# W107X.net
KiCad netlist of a schematic drawn in EAGLE
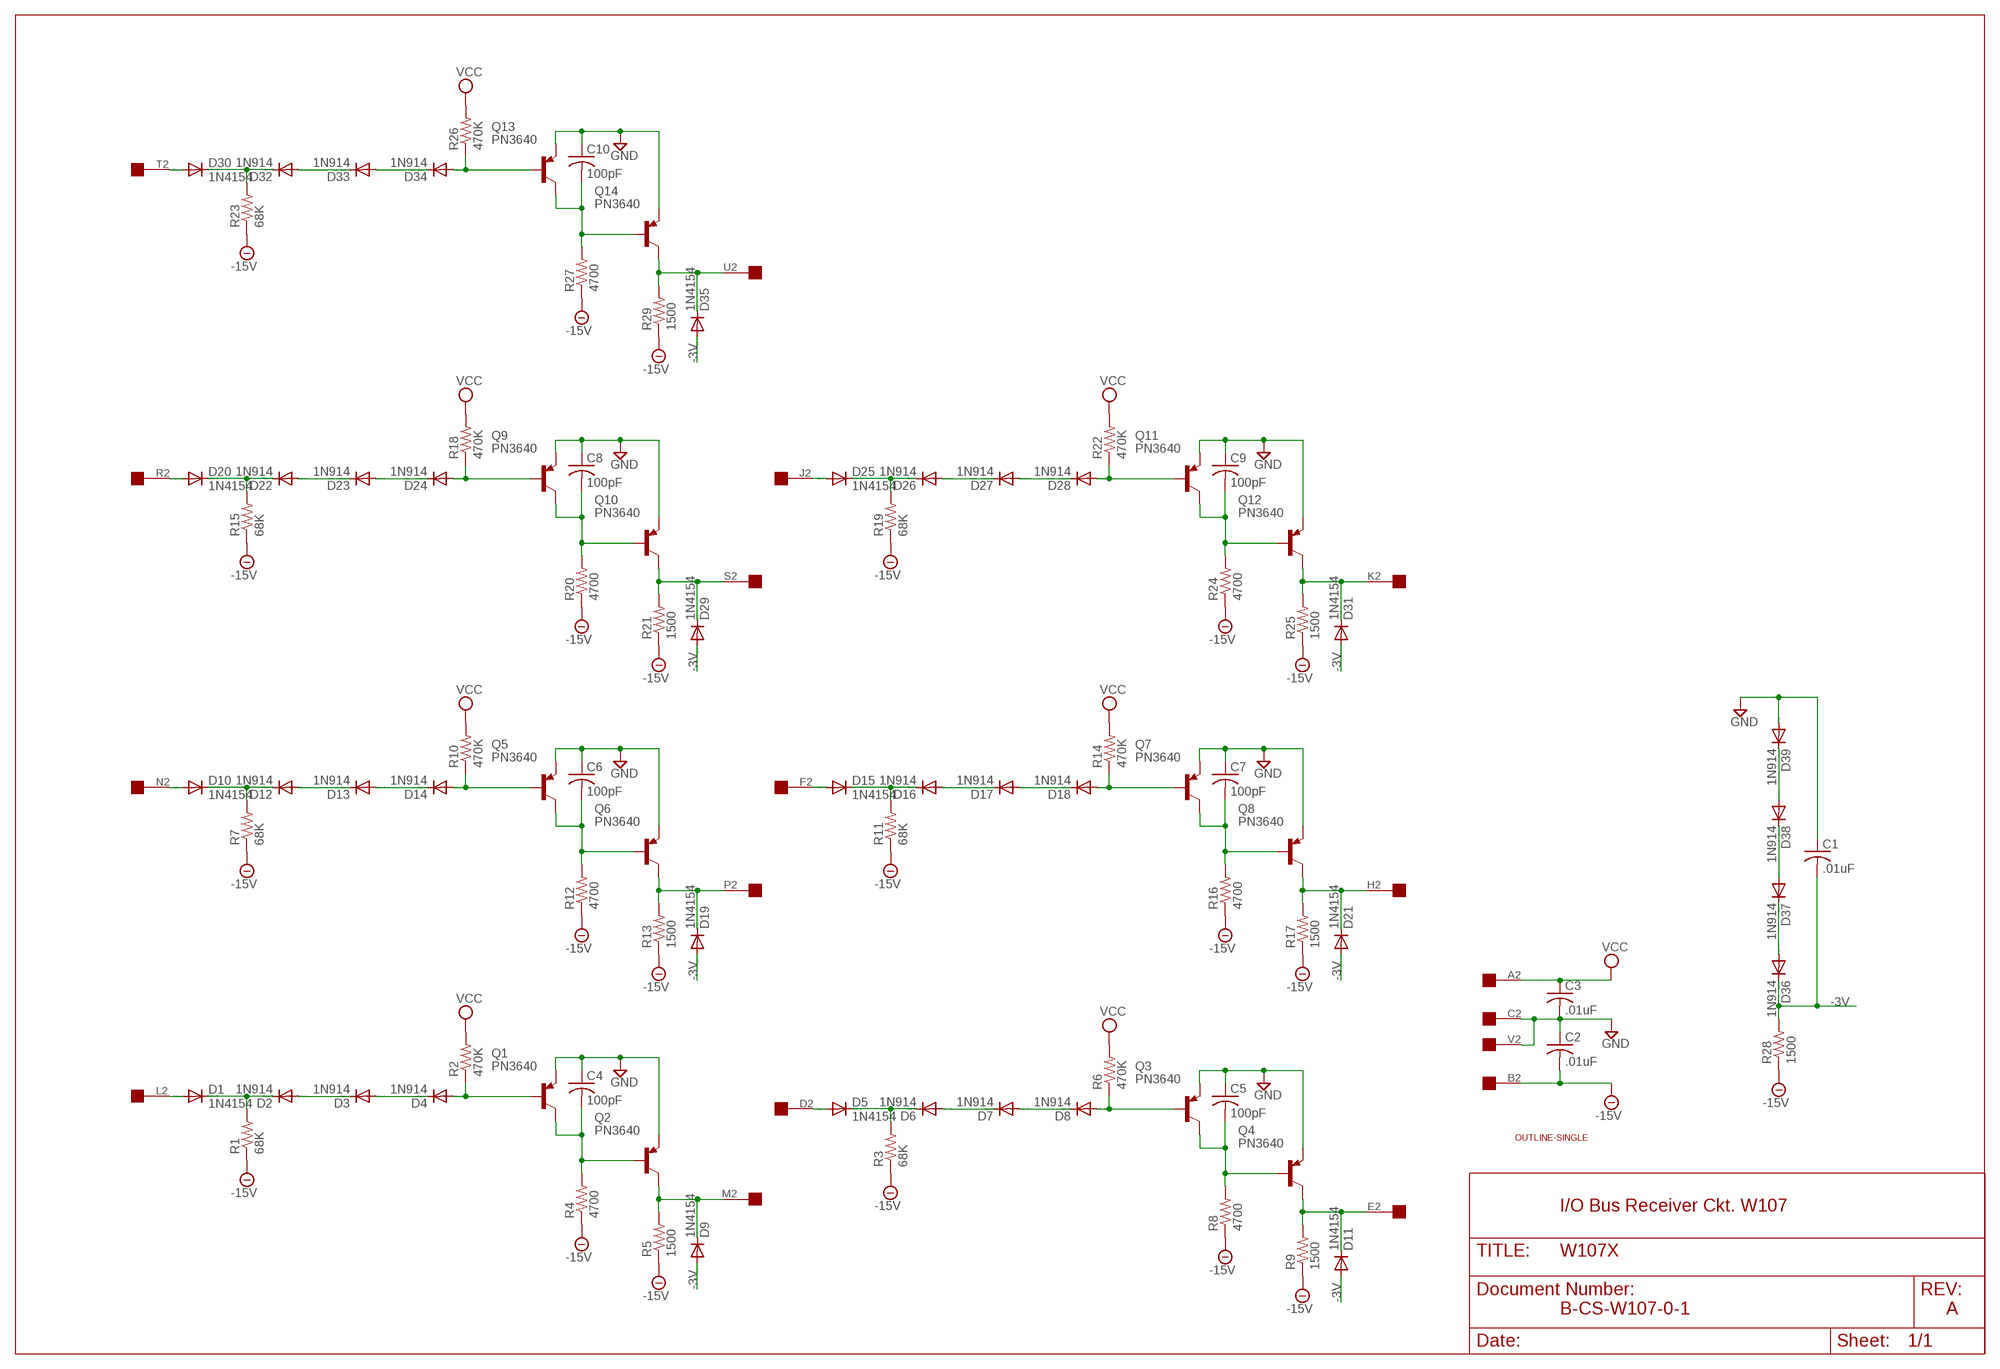
[diagram p0: schematic, sheet 1]

(export (version "E")
  (design (tool "Eeschema 10.0.6"))
  (components
    (comp (ref "C1")
      (value ".01uF")
      (footprint "eagle-import:C063-025X075")
      (libsource (lib "eagle-import") (part "C-US"))
    )
    (comp (ref "C2")
      (value ".01uF")
      (footprint "eagle-import:C063-025X075")
      (libsource (lib "eagle-import") (part "C-US"))
    )
    (comp (ref "C3")
      (value ".01uF")
      (footprint "eagle-import:C063-025X075")
      (libsource (lib "eagle-import") (part "C-US"))
    )
    (comp (ref "C4")
      (value "100pF")
      (footprint "eagle-import:C063-025X075")
      (libsource (lib "eagle-import") (part "C-US"))
    )
    (comp (ref "C5")
      (value "100pF")
      (footprint "eagle-import:C063-025X075")
      (libsource (lib "eagle-import") (part "C-US"))
    )
    (comp (ref "C6")
      (value "100pF")
      (footprint "eagle-import:C063-025X075")
      (libsource (lib "eagle-import") (part "C-US"))
    )
    (comp (ref "C7")
      (value "100pF")
      (footprint "eagle-import:C063-025X075")
      (libsource (lib "eagle-import") (part "C-US"))
    )
    (comp (ref "C8")
      (value "100pF")
      (footprint "eagle-import:C063-025X075")
      (libsource (lib "eagle-import") (part "C-US"))
    )
    (comp (ref "C9")
      (value "100pF")
      (footprint "eagle-import:C063-025X075")
      (libsource (lib "eagle-import") (part "C-US"))
    )
    (comp (ref "C10")
      (value "100pF")
      (footprint "eagle-import:C063-025X075")
      (libsource (lib "eagle-import") (part "C-US"))
    )
    (comp (ref "D1")
      (value "1N4154")
      (footprint "eagle-import:DO35-10")
      (libsource (lib "eagle-import") (part "DIODE-DO35-10"))
    )
    (comp (ref "D2")
      (value "1N914")
      (footprint "eagle-import:DO35-10")
      (libsource (lib "eagle-import") (part "DIODE-DO35-10"))
    )
    (comp (ref "D3")
      (value "1N914")
      (footprint "eagle-import:DO35-10")
      (libsource (lib "eagle-import") (part "DIODE-DO35-10"))
    )
    (comp (ref "D4")
      (value "1N914")
      (footprint "eagle-import:DO35-10")
      (libsource (lib "eagle-import") (part "DIODE-DO35-10"))
    )
    (comp (ref "D5")
      (value "1N4154")
      (footprint "eagle-import:DO35-10")
      (libsource (lib "eagle-import") (part "DIODE-DO35-10"))
    )
    (comp (ref "D6")
      (value "1N914")
      (footprint "eagle-import:DO35-10")
      (libsource (lib "eagle-import") (part "DIODE-DO35-10"))
    )
    (comp (ref "D7")
      (value "1N914")
      (footprint "eagle-import:DO35-10")
      (libsource (lib "eagle-import") (part "DIODE-DO35-10"))
    )
    (comp (ref "D8")
      (value "1N914")
      (footprint "eagle-import:DO35-10")
      (libsource (lib "eagle-import") (part "DIODE-DO35-10"))
    )
    (comp (ref "D9")
      (value "1N4154")
      (footprint "eagle-import:DO35-10")
      (libsource (lib "eagle-import") (part "DIODE-DO35-10"))
    )
    (comp (ref "D10")
      (value "1N4154")
      (footprint "eagle-import:DO35-10")
      (libsource (lib "eagle-import") (part "DIODE-DO35-10"))
    )
    (comp (ref "D11")
      (value "1N4154")
      (footprint "eagle-import:DO35-10")
      (libsource (lib "eagle-import") (part "DIODE-DO35-10"))
    )
    (comp (ref "D12")
      (value "1N914")
      (footprint "eagle-import:DO35-10")
      (libsource (lib "eagle-import") (part "DIODE-DO35-10"))
    )
    (comp (ref "D13")
      (value "1N914")
      (footprint "eagle-import:DO35-10")
      (libsource (lib "eagle-import") (part "DIODE-DO35-10"))
    )
    (comp (ref "D14")
      (value "1N914")
      (footprint "eagle-import:DO35-10")
      (libsource (lib "eagle-import") (part "DIODE-DO35-10"))
    )
    (comp (ref "D15")
      (value "1N4154")
      (footprint "eagle-import:DO35-10")
      (libsource (lib "eagle-import") (part "DIODE-DO35-10"))
    )
    (comp (ref "D16")
      (value "1N914")
      (footprint "eagle-import:DO35-10")
      (libsource (lib "eagle-import") (part "DIODE-DO35-10"))
    )
    (comp (ref "D17")
      (value "1N914")
      (footprint "eagle-import:DO35-10")
      (libsource (lib "eagle-import") (part "DIODE-DO35-10"))
    )
    (comp (ref "D18")
      (value "1N914")
      (footprint "eagle-import:DO35-10")
      (libsource (lib "eagle-import") (part "DIODE-DO35-10"))
    )
    (comp (ref "D19")
      (value "1N4154")
      (footprint "eagle-import:DO35-10")
      (libsource (lib "eagle-import") (part "DIODE-DO35-10"))
    )
    (comp (ref "D20")
      (value "1N4154")
      (footprint "eagle-import:DO35-10")
      (libsource (lib "eagle-import") (part "DIODE-DO35-10"))
    )
    (comp (ref "D21")
      (value "1N4154")
      (footprint "eagle-import:DO35-10")
      (libsource (lib "eagle-import") (part "DIODE-DO35-10"))
    )
    (comp (ref "D22")
      (value "1N914")
      (footprint "eagle-import:DO35-10")
      (libsource (lib "eagle-import") (part "DIODE-DO35-10"))
    )
    (comp (ref "D23")
      (value "1N914")
      (footprint "eagle-import:DO35-10")
      (libsource (lib "eagle-import") (part "DIODE-DO35-10"))
    )
    (comp (ref "D24")
      (value "1N914")
      (footprint "eagle-import:DO35-10")
      (libsource (lib "eagle-import") (part "DIODE-DO35-10"))
    )
    (comp (ref "D25")
      (value "1N4154")
      (footprint "eagle-import:DO35-10")
      (libsource (lib "eagle-import") (part "DIODE-DO35-10"))
    )
    (comp (ref "D26")
      (value "1N914")
      (footprint "eagle-import:DO35-10")
      (libsource (lib "eagle-import") (part "DIODE-DO35-10"))
    )
    (comp (ref "D27")
      (value "1N914")
      (footprint "eagle-import:DO35-10")
      (libsource (lib "eagle-import") (part "DIODE-DO35-10"))
    )
    (comp (ref "D28")
      (value "1N914")
      (footprint "eagle-import:DO35-10")
      (libsource (lib "eagle-import") (part "DIODE-DO35-10"))
    )
    (comp (ref "D29")
      (value "1N4154")
      (footprint "eagle-import:DO35-10")
      (libsource (lib "eagle-import") (part "DIODE-DO35-10"))
    )
    (comp (ref "D30")
      (value "1N4154")
      (footprint "eagle-import:DO35-10")
      (libsource (lib "eagle-import") (part "DIODE-DO35-10"))
    )
    (comp (ref "D31")
      (value "1N4154")
      (footprint "eagle-import:DO35-10")
      (libsource (lib "eagle-import") (part "DIODE-DO35-10"))
    )
    (comp (ref "D32")
      (value "1N914")
      (footprint "eagle-import:DO35-10")
      (libsource (lib "eagle-import") (part "DIODE-DO35-10"))
    )
    (comp (ref "D33")
      (value "1N914")
      (footprint "eagle-import:DO35-10")
      (libsource (lib "eagle-import") (part "DIODE-DO35-10"))
    )
    (comp (ref "D34")
      (value "1N914")
      (footprint "eagle-import:DO35-10")
      (libsource (lib "eagle-import") (part "DIODE-DO35-10"))
    )
    (comp (ref "D35")
      (value "1N4154")
      (footprint "eagle-import:DO35-10")
      (libsource (lib "eagle-import") (part "DIODE-DO35-10"))
    )
    (comp (ref "D36")
      (value "1N914")
      (footprint "eagle-import:DO35-10")
      (libsource (lib "eagle-import") (part "DIODE-DO35-10"))
    )
    (comp (ref "D37")
      (value "1N914")
      (footprint "eagle-import:DO35-10")
      (libsource (lib "eagle-import") (part "DIODE-DO35-10"))
    )
    (comp (ref "D38")
      (value "1N914")
      (footprint "eagle-import:DO35-10")
      (libsource (lib "eagle-import") (part "DIODE-DO35-10"))
    )
    (comp (ref "D39")
      (value "1N914")
      (footprint "eagle-import:DO35-10")
      (libsource (lib "eagle-import") (part "DIODE-DO35-10"))
    )
    (comp (ref "Q1")
      (value "PN3640")
      (footprint "eagle-import:TO5")
      (libsource (lib "eagle-import") (part "-PNP-TO5"))
    )
    (comp (ref "Q2")
      (value "PN3640")
      (footprint "eagle-import:TO5")
      (libsource (lib "eagle-import") (part "-PNP-TO5"))
    )
    (comp (ref "Q3")
      (value "PN3640")
      (footprint "eagle-import:TO5")
      (libsource (lib "eagle-import") (part "-PNP-TO5"))
    )
    (comp (ref "Q4")
      (value "PN3640")
      (footprint "eagle-import:TO5")
      (libsource (lib "eagle-import") (part "-PNP-TO5"))
    )
    (comp (ref "Q5")
      (value "PN3640")
      (footprint "eagle-import:TO5")
      (libsource (lib "eagle-import") (part "-PNP-TO5"))
    )
    (comp (ref "Q6")
      (value "PN3640")
      (footprint "eagle-import:TO5")
      (libsource (lib "eagle-import") (part "-PNP-TO5"))
    )
    (comp (ref "Q7")
      (value "PN3640")
      (footprint "eagle-import:TO5")
      (libsource (lib "eagle-import") (part "-PNP-TO5"))
    )
    (comp (ref "Q8")
      (value "PN3640")
      (footprint "eagle-import:TO5")
      (libsource (lib "eagle-import") (part "-PNP-TO5"))
    )
    (comp (ref "Q9")
      (value "PN3640")
      (footprint "eagle-import:TO5")
      (libsource (lib "eagle-import") (part "-PNP-TO5"))
    )
    (comp (ref "Q10")
      (value "PN3640")
      (footprint "eagle-import:TO5")
      (libsource (lib "eagle-import") (part "-PNP-TO5"))
    )
    (comp (ref "Q11")
      (value "PN3640")
      (footprint "eagle-import:TO5")
      (libsource (lib "eagle-import") (part "-PNP-TO5"))
    )
    (comp (ref "Q12")
      (value "PN3640")
      (footprint "eagle-import:TO5")
      (libsource (lib "eagle-import") (part "-PNP-TO5"))
    )
    (comp (ref "Q13")
      (value "PN3640")
      (footprint "eagle-import:TO5")
      (libsource (lib "eagle-import") (part "-PNP-TO5"))
    )
    (comp (ref "Q14")
      (value "PN3640")
      (footprint "eagle-import:TO5")
      (libsource (lib "eagle-import") (part "-PNP-TO5"))
    )
    (comp (ref "R1")
      (value "68K")
      (footprint "eagle-import:0207_10")
      (libsource (lib "eagle-import") (part "R-US_0207/10"))
    )
    (comp (ref "R2")
      (value "470K")
      (footprint "eagle-import:0207_10")
      (libsource (lib "eagle-import") (part "R-US_0207/10"))
    )
    (comp (ref "R3")
      (value "68K")
      (footprint "eagle-import:0207_10")
      (libsource (lib "eagle-import") (part "R-US_0207/10"))
    )
    (comp (ref "R4")
      (value "4700")
      (footprint "eagle-import:0207_10")
      (libsource (lib "eagle-import") (part "R-US_0207/10"))
    )
    (comp (ref "R5")
      (value "1500")
      (footprint "eagle-import:0207_10")
      (libsource (lib "eagle-import") (part "R-US_0207/10"))
    )
    (comp (ref "R6")
      (value "470K")
      (footprint "eagle-import:0207_10")
      (libsource (lib "eagle-import") (part "R-US_0207/10"))
    )
    (comp (ref "R7")
      (value "68K")
      (footprint "eagle-import:0207_10")
      (libsource (lib "eagle-import") (part "R-US_0207/10"))
    )
    (comp (ref "R8")
      (value "4700")
      (footprint "eagle-import:0207_10")
      (libsource (lib "eagle-import") (part "R-US_0207/10"))
    )
    (comp (ref "R9")
      (value "1500")
      (footprint "eagle-import:0207_10")
      (libsource (lib "eagle-import") (part "R-US_0207/10"))
    )
    (comp (ref "R10")
      (value "470K")
      (footprint "eagle-import:0207_10")
      (libsource (lib "eagle-import") (part "R-US_0207/10"))
    )
    (comp (ref "R11")
      (value "68K")
      (footprint "eagle-import:0207_10")
      (libsource (lib "eagle-import") (part "R-US_0207/10"))
    )
    (comp (ref "R12")
      (value "4700")
      (footprint "eagle-import:0207_10")
      (libsource (lib "eagle-import") (part "R-US_0207/10"))
    )
    (comp (ref "R13")
      (value "1500")
      (footprint "eagle-import:0207_10")
      (libsource (lib "eagle-import") (part "R-US_0207/10"))
    )
    (comp (ref "R14")
      (value "470K")
      (footprint "eagle-import:0207_10")
      (libsource (lib "eagle-import") (part "R-US_0207/10"))
    )
    (comp (ref "R15")
      (value "68K")
      (footprint "eagle-import:0207_10")
      (libsource (lib "eagle-import") (part "R-US_0207/10"))
    )
    (comp (ref "R16")
      (value "4700")
      (footprint "eagle-import:0207_10")
      (libsource (lib "eagle-import") (part "R-US_0207/10"))
    )
    (comp (ref "R17")
      (value "1500")
      (footprint "eagle-import:0207_10")
      (libsource (lib "eagle-import") (part "R-US_0207/10"))
    )
    (comp (ref "R18")
      (value "470K")
      (footprint "eagle-import:0207_10")
      (libsource (lib "eagle-import") (part "R-US_0207/10"))
    )
    (comp (ref "R19")
      (value "68K")
      (footprint "eagle-import:0207_10")
      (libsource (lib "eagle-import") (part "R-US_0207/10"))
    )
    (comp (ref "R20")
      (value "4700")
      (footprint "eagle-import:0207_10")
      (libsource (lib "eagle-import") (part "R-US_0207/10"))
    )
    (comp (ref "R21")
      (value "1500")
      (footprint "eagle-import:0207_10")
      (libsource (lib "eagle-import") (part "R-US_0207/10"))
    )
    (comp (ref "R22")
      (value "470K")
      (footprint "eagle-import:0207_10")
      (libsource (lib "eagle-import") (part "R-US_0207/10"))
    )
    (comp (ref "R23")
      (value "68K")
      (footprint "eagle-import:0207_10")
      (libsource (lib "eagle-import") (part "R-US_0207/10"))
    )
    (comp (ref "R24")
      (value "4700")
      (footprint "eagle-import:0207_10")
      (libsource (lib "eagle-import") (part "R-US_0207/10"))
    )
    (comp (ref "R25")
      (value "1500")
      (footprint "eagle-import:0207_10")
      (libsource (lib "eagle-import") (part "R-US_0207/10"))
    )
    (comp (ref "R26")
      (value "470K")
      (footprint "eagle-import:0207_10")
      (libsource (lib "eagle-import") (part "R-US_0207/10"))
    )
    (comp (ref "R27")
      (value "4700")
      (footprint "eagle-import:0207_10")
      (libsource (lib "eagle-import") (part "R-US_0207/10"))
    )
    (comp (ref "R28")
      (value "1500")
      (footprint "eagle-import:0207_10")
      (libsource (lib "eagle-import") (part "R-US_0207/10"))
    )
    (comp (ref "R29")
      (value "1500")
      (footprint "eagle-import:0207_10")
      (libsource (lib "eagle-import") (part "R-US_0207/10"))
    )
    (comp (ref "U$1")
      (value "OUTLINE-SINGLE")
      (footprint "eagle-import:SINGLE")
      (libsource (lib "eagle-import") (part "OUTLINE-SINGLE"))
    )
    (comp (ref "U$2")
      (value "EDGE-1")
      (footprint "eagle-import:EDGE-CON1")
      (libsource (lib "eagle-import") (part "EDGE-1"))
    )
  )
  (nets
    (net (code "1") (name "-15V") (class "Default")
      (node (ref "C2") (pin "2") (pinfunction "2_2") (pintype "passive"))
      (node (ref "R1") (pin "1") (pinfunction "1_1") (pintype "passive"))
      (node (ref "R11") (pin "1") (pinfunction "1_1") (pintype "passive"))
      (node (ref "R12") (pin "1") (pinfunction "1_1") (pintype "passive"))
      (node (ref "R13") (pin "1") (pinfunction "1_1") (pintype "passive"))
      (node (ref "R15") (pin "1") (pinfunction "1_1") (pintype "passive"))
      (node (ref "R16") (pin "1") (pinfunction "1_1") (pintype "passive"))
      (node (ref "R17") (pin "1") (pinfunction "1_1") (pintype "passive"))
      (node (ref "R19") (pin "1") (pinfunction "1_1") (pintype "passive"))
      (node (ref "R20") (pin "1") (pinfunction "1_1") (pintype "passive"))
      (node (ref "R21") (pin "1") (pinfunction "1_1") (pintype "passive"))
      (node (ref "R23") (pin "1") (pinfunction "1_1") (pintype "passive"))
      (node (ref "R24") (pin "1") (pinfunction "1_1") (pintype "passive"))
      (node (ref "R25") (pin "1") (pinfunction "1_1") (pintype "passive"))
      (node (ref "R27") (pin "1") (pinfunction "1_1") (pintype "passive"))
      (node (ref "R28") (pin "1") (pinfunction "1_1") (pintype "passive"))
      (node (ref "R29") (pin "1") (pinfunction "1_1") (pintype "passive"))
      (node (ref "R3") (pin "1") (pinfunction "1_1") (pintype "passive"))
      (node (ref "R4") (pin "1") (pinfunction "1_1") (pintype "passive"))
      (node (ref "R5") (pin "1") (pinfunction "1_1") (pintype "passive"))
      (node (ref "R7") (pin "1") (pinfunction "1_1") (pintype "passive"))
      (node (ref "R8") (pin "1") (pinfunction "1_1") (pintype "passive"))
      (node (ref "R9") (pin "1") (pinfunction "1_1") (pintype "passive"))
      (node (ref "U$2") (pin "B2") (pinfunction "1_B2") (pintype "bidirectional"))
    )
    (net (code "2") (name "/-3V") (class "Default")
      (node (ref "C1") (pin "2") (pinfunction "2_2") (pintype "passive"))
      (node (ref "D11") (pin "A") (pinfunction "A_A") (pintype "passive"))
      (node (ref "D19") (pin "A") (pinfunction "A_A") (pintype "passive"))
      (node (ref "D21") (pin "A") (pinfunction "A_A") (pintype "passive"))
      (node (ref "D29") (pin "A") (pinfunction "A_A") (pintype "passive"))
      (node (ref "D31") (pin "A") (pinfunction "A_A") (pintype "passive"))
      (node (ref "D35") (pin "A") (pinfunction "A_A") (pintype "passive"))
      (node (ref "D36") (pin "C") (pinfunction "C_C") (pintype "passive"))
      (node (ref "D9") (pin "A") (pinfunction "A_A") (pintype "passive"))
      (node (ref "R28") (pin "2") (pinfunction "2_2") (pintype "passive"))
    )
    (net (code "3") (name "GND") (class "Default")
      (node (ref "C1") (pin "1") (pinfunction "1_1") (pintype "passive"))
      (node (ref "C10") (pin "1") (pinfunction "1_1") (pintype "passive"))
      (node (ref "C2") (pin "1") (pinfunction "1_1") (pintype "passive"))
      (node (ref "C3") (pin "2") (pinfunction "2_2") (pintype "passive"))
      (node (ref "C4") (pin "1") (pinfunction "1_1") (pintype "passive"))
      (node (ref "C5") (pin "1") (pinfunction "1_1") (pintype "passive"))
      (node (ref "C6") (pin "1") (pinfunction "1_1") (pintype "passive"))
      (node (ref "C7") (pin "1") (pinfunction "1_1") (pintype "passive"))
      (node (ref "C8") (pin "1") (pinfunction "1_1") (pintype "passive"))
      (node (ref "C9") (pin "1") (pinfunction "1_1") (pintype "passive"))
      (node (ref "D39") (pin "A") (pinfunction "A_A") (pintype "passive"))
      (node (ref "Q1") (pin "1") (pinfunction "E_1") (pintype "passive"))
      (node (ref "Q10") (pin "1") (pinfunction "E_1") (pintype "passive"))
      (node (ref "Q11") (pin "1") (pinfunction "E_1") (pintype "passive"))
      (node (ref "Q12") (pin "1") (pinfunction "E_1") (pintype "passive"))
      (node (ref "Q13") (pin "1") (pinfunction "E_1") (pintype "passive"))
      (node (ref "Q14") (pin "1") (pinfunction "E_1") (pintype "passive"))
      (node (ref "Q2") (pin "1") (pinfunction "E_1") (pintype "passive"))
      (node (ref "Q3") (pin "1") (pinfunction "E_1") (pintype "passive"))
      (node (ref "Q4") (pin "1") (pinfunction "E_1") (pintype "passive"))
      (node (ref "Q5") (pin "1") (pinfunction "E_1") (pintype "passive"))
      (node (ref "Q6") (pin "1") (pinfunction "E_1") (pintype "passive"))
      (node (ref "Q7") (pin "1") (pinfunction "E_1") (pintype "passive"))
      (node (ref "Q8") (pin "1") (pinfunction "E_1") (pintype "passive"))
      (node (ref "Q9") (pin "1") (pinfunction "E_1") (pintype "passive"))
      (node (ref "U$2") (pin "C2") (pinfunction "1_C2") (pintype "bidirectional"))
      (node (ref "U$2") (pin "V2") (pinfunction "1_V2") (pintype "bidirectional"))
    )
    (net (code "4") (name "Net-(D1-PadC)") (class "Default")
      (node (ref "D1") (pin "C") (pinfunction "C_C") (pintype "passive"))
      (node (ref "D2") (pin "C") (pinfunction "C_C") (pintype "passive"))
      (node (ref "R1") (pin "2") (pinfunction "2_2") (pintype "passive"))
    )
    (net (code "5") (name "Net-(D2-PadA)") (class "Default")
      (node (ref "D2") (pin "A") (pinfunction "A_A") (pintype "passive"))
      (node (ref "D3") (pin "C") (pinfunction "C_C") (pintype "passive"))
    )
    (net (code "6") (name "Net-(D3-PadA)") (class "Default")
      (node (ref "D3") (pin "A") (pinfunction "A_A") (pintype "passive"))
      (node (ref "D4") (pin "C") (pinfunction "C_C") (pintype "passive"))
    )
    (net (code "7") (name "Net-(D5-PadC)") (class "Default")
      (node (ref "D5") (pin "C") (pinfunction "C_C") (pintype "passive"))
      (node (ref "D6") (pin "C") (pinfunction "C_C") (pintype "passive"))
      (node (ref "R3") (pin "2") (pinfunction "2_2") (pintype "passive"))
    )
    (net (code "8") (name "Net-(D6-PadA)") (class "Default")
      (node (ref "D6") (pin "A") (pinfunction "A_A") (pintype "passive"))
      (node (ref "D7") (pin "C") (pinfunction "C_C") (pintype "passive"))
    )
    (net (code "9") (name "Net-(D7-PadA)") (class "Default")
      (node (ref "D7") (pin "A") (pinfunction "A_A") (pintype "passive"))
      (node (ref "D8") (pin "C") (pinfunction "C_C") (pintype "passive"))
    )
    (net (code "10") (name "Net-(D10-PadC)") (class "Default")
      (node (ref "D10") (pin "C") (pinfunction "C_C") (pintype "passive"))
      (node (ref "D12") (pin "C") (pinfunction "C_C") (pintype "passive"))
      (node (ref "R7") (pin "2") (pinfunction "2_2") (pintype "passive"))
    )
    (net (code "11") (name "Net-(D12-PadA)") (class "Default")
      (node (ref "D12") (pin "A") (pinfunction "A_A") (pintype "passive"))
      (node (ref "D13") (pin "C") (pinfunction "C_C") (pintype "passive"))
    )
    (net (code "12") (name "Net-(D13-PadA)") (class "Default")
      (node (ref "D13") (pin "A") (pinfunction "A_A") (pintype "passive"))
      (node (ref "D14") (pin "C") (pinfunction "C_C") (pintype "passive"))
    )
    (net (code "13") (name "Net-(D15-PadC)") (class "Default")
      (node (ref "D15") (pin "C") (pinfunction "C_C") (pintype "passive"))
      (node (ref "D16") (pin "C") (pinfunction "C_C") (pintype "passive"))
      (node (ref "R11") (pin "2") (pinfunction "2_2") (pintype "passive"))
    )
    (net (code "14") (name "Net-(D16-PadA)") (class "Default")
      (node (ref "D16") (pin "A") (pinfunction "A_A") (pintype "passive"))
      (node (ref "D17") (pin "C") (pinfunction "C_C") (pintype "passive"))
    )
    (net (code "15") (name "Net-(D17-PadA)") (class "Default")
      (node (ref "D17") (pin "A") (pinfunction "A_A") (pintype "passive"))
      (node (ref "D18") (pin "C") (pinfunction "C_C") (pintype "passive"))
    )
    (net (code "16") (name "Net-(D20-PadC)") (class "Default")
      (node (ref "D20") (pin "C") (pinfunction "C_C") (pintype "passive"))
      (node (ref "D22") (pin "C") (pinfunction "C_C") (pintype "passive"))
      (node (ref "R15") (pin "2") (pinfunction "2_2") (pintype "passive"))
    )
    (net (code "17") (name "Net-(D22-PadA)") (class "Default")
      (node (ref "D22") (pin "A") (pinfunction "A_A") (pintype "passive"))
      (node (ref "D23") (pin "C") (pinfunction "C_C") (pintype "passive"))
    )
    (net (code "18") (name "Net-(D23-PadA)") (class "Default")
      (node (ref "D23") (pin "A") (pinfunction "A_A") (pintype "passive"))
      (node (ref "D24") (pin "C") (pinfunction "C_C") (pintype "passive"))
    )
    (net (code "19") (name "Net-(D25-PadC)") (class "Default")
      (node (ref "D25") (pin "C") (pinfunction "C_C") (pintype "passive"))
      (node (ref "D26") (pin "C") (pinfunction "C_C") (pintype "passive"))
      (node (ref "R19") (pin "2") (pinfunction "2_2") (pintype "passive"))
    )
    (net (code "20") (name "Net-(D26-PadA)") (class "Default")
      (node (ref "D26") (pin "A") (pinfunction "A_A") (pintype "passive"))
      (node (ref "D27") (pin "C") (pinfunction "C_C") (pintype "passive"))
    )
    (net (code "21") (name "Net-(D27-PadA)") (class "Default")
      (node (ref "D27") (pin "A") (pinfunction "A_A") (pintype "passive"))
      (node (ref "D28") (pin "C") (pinfunction "C_C") (pintype "passive"))
    )
    (net (code "22") (name "Net-(D30-PadC)") (class "Default")
      (node (ref "D30") (pin "C") (pinfunction "C_C") (pintype "passive"))
      (node (ref "D32") (pin "C") (pinfunction "C_C") (pintype "passive"))
      (node (ref "R23") (pin "2") (pinfunction "2_2") (pintype "passive"))
    )
    (net (code "23") (name "Net-(D32-PadA)") (class "Default")
      (node (ref "D32") (pin "A") (pinfunction "A_A") (pintype "passive"))
      (node (ref "D33") (pin "C") (pinfunction "C_C") (pintype "passive"))
    )
    (net (code "24") (name "Net-(D33-PadA)") (class "Default")
      (node (ref "D33") (pin "A") (pinfunction "A_A") (pintype "passive"))
      (node (ref "D34") (pin "C") (pinfunction "C_C") (pintype "passive"))
    )
    (net (code "25") (name "Net-(D36-PadA)") (class "Default")
      (node (ref "D36") (pin "A") (pinfunction "A_A") (pintype "passive"))
      (node (ref "D37") (pin "C") (pinfunction "C_C") (pintype "passive"))
    )
    (net (code "26") (name "Net-(D37-PadA)") (class "Default")
      (node (ref "D37") (pin "A") (pinfunction "A_A") (pintype "passive"))
      (node (ref "D38") (pin "C") (pinfunction "C_C") (pintype "passive"))
    )
    (net (code "27") (name "Net-(D38-PadA)") (class "Default")
      (node (ref "D38") (pin "A") (pinfunction "A_A") (pintype "passive"))
      (node (ref "D39") (pin "C") (pinfunction "C_C") (pintype "passive"))
    )
    (net (code "28") (name "Net-(Q1-B)") (class "Default")
      (node (ref "D4") (pin "A") (pinfunction "A_A") (pintype "passive"))
      (node (ref "Q1") (pin "2") (pinfunction "B_2") (pintype "passive"))
      (node (ref "R2") (pin "1") (pinfunction "1_1") (pintype "passive"))
    )
    (net (code "29") (name "Net-(Q1-C)") (class "Default")
      (node (ref "C4") (pin "2") (pinfunction "2_2") (pintype "passive"))
      (node (ref "Q1") (pin "3") (pinfunction "C_3") (pintype "passive"))
      (node (ref "Q2") (pin "2") (pinfunction "B_2") (pintype "passive"))
      (node (ref "R4") (pin "2") (pinfunction "2_2") (pintype "passive"))
    )
    (net (code "30") (name "Net-(Q2-C)") (class "Default")
      (node (ref "D9") (pin "C") (pinfunction "C_C") (pintype "passive"))
      (node (ref "Q2") (pin "3") (pinfunction "C_3") (pintype "passive"))
      (node (ref "R5") (pin "2") (pinfunction "2_2") (pintype "passive"))
      (node (ref "U$2") (pin "M2") (pinfunction "1_M2") (pintype "bidirectional"))
    )
    (net (code "31") (name "Net-(Q3-B)") (class "Default")
      (node (ref "D8") (pin "A") (pinfunction "A_A") (pintype "passive"))
      (node (ref "Q3") (pin "2") (pinfunction "B_2") (pintype "passive"))
      (node (ref "R6") (pin "1") (pinfunction "1_1") (pintype "passive"))
    )
    (net (code "32") (name "Net-(Q3-C)") (class "Default")
      (node (ref "C5") (pin "2") (pinfunction "2_2") (pintype "passive"))
      (node (ref "Q3") (pin "3") (pinfunction "C_3") (pintype "passive"))
      (node (ref "Q4") (pin "2") (pinfunction "B_2") (pintype "passive"))
      (node (ref "R8") (pin "2") (pinfunction "2_2") (pintype "passive"))
    )
    (net (code "33") (name "Net-(Q4-C)") (class "Default")
      (node (ref "D11") (pin "C") (pinfunction "C_C") (pintype "passive"))
      (node (ref "Q4") (pin "3") (pinfunction "C_3") (pintype "passive"))
      (node (ref "R9") (pin "2") (pinfunction "2_2") (pintype "passive"))
      (node (ref "U$2") (pin "E2") (pinfunction "1_E2") (pintype "bidirectional"))
    )
    (net (code "34") (name "Net-(Q5-B)") (class "Default")
      (node (ref "D14") (pin "A") (pinfunction "A_A") (pintype "passive"))
      (node (ref "Q5") (pin "2") (pinfunction "B_2") (pintype "passive"))
      (node (ref "R10") (pin "1") (pinfunction "1_1") (pintype "passive"))
    )
    (net (code "35") (name "Net-(Q5-C)") (class "Default")
      (node (ref "C6") (pin "2") (pinfunction "2_2") (pintype "passive"))
      (node (ref "Q5") (pin "3") (pinfunction "C_3") (pintype "passive"))
      (node (ref "Q6") (pin "2") (pinfunction "B_2") (pintype "passive"))
      (node (ref "R12") (pin "2") (pinfunction "2_2") (pintype "passive"))
    )
    (net (code "36") (name "Net-(Q6-C)") (class "Default")
      (node (ref "D19") (pin "C") (pinfunction "C_C") (pintype "passive"))
      (node (ref "Q6") (pin "3") (pinfunction "C_3") (pintype "passive"))
      (node (ref "R13") (pin "2") (pinfunction "2_2") (pintype "passive"))
      (node (ref "U$2") (pin "P2") (pinfunction "1_P2") (pintype "bidirectional"))
    )
    (net (code "37") (name "Net-(Q7-B)") (class "Default")
      (node (ref "D18") (pin "A") (pinfunction "A_A") (pintype "passive"))
      (node (ref "Q7") (pin "2") (pinfunction "B_2") (pintype "passive"))
      (node (ref "R14") (pin "1") (pinfunction "1_1") (pintype "passive"))
    )
    (net (code "38") (name "Net-(Q7-C)") (class "Default")
      (node (ref "C7") (pin "2") (pinfunction "2_2") (pintype "passive"))
      (node (ref "Q7") (pin "3") (pinfunction "C_3") (pintype "passive"))
      (node (ref "Q8") (pin "2") (pinfunction "B_2") (pintype "passive"))
      (node (ref "R16") (pin "2") (pinfunction "2_2") (pintype "passive"))
    )
    (net (code "39") (name "Net-(Q8-C)") (class "Default")
      (node (ref "D21") (pin "C") (pinfunction "C_C") (pintype "passive"))
      (node (ref "Q8") (pin "3") (pinfunction "C_3") (pintype "passive"))
      (node (ref "R17") (pin "2") (pinfunction "2_2") (pintype "passive"))
      (node (ref "U$2") (pin "H2") (pinfunction "1_H2") (pintype "bidirectional"))
    )
    (net (code "40") (name "Net-(Q9-B)") (class "Default")
      (node (ref "D24") (pin "A") (pinfunction "A_A") (pintype "passive"))
      (node (ref "Q9") (pin "2") (pinfunction "B_2") (pintype "passive"))
      (node (ref "R18") (pin "1") (pinfunction "1_1") (pintype "passive"))
    )
    (net (code "41") (name "Net-(Q10-B)") (class "Default")
      (node (ref "C8") (pin "2") (pinfunction "2_2") (pintype "passive"))
      (node (ref "Q10") (pin "2") (pinfunction "B_2") (pintype "passive"))
      (node (ref "Q9") (pin "3") (pinfunction "C_3") (pintype "passive"))
      (node (ref "R20") (pin "2") (pinfunction "2_2") (pintype "passive"))
    )
    (net (code "42") (name "Net-(Q10-C)") (class "Default")
      (node (ref "D29") (pin "C") (pinfunction "C_C") (pintype "passive"))
      (node (ref "Q10") (pin "3") (pinfunction "C_3") (pintype "passive"))
      (node (ref "R21") (pin "2") (pinfunction "2_2") (pintype "passive"))
      (node (ref "U$2") (pin "S2") (pinfunction "1_S2") (pintype "bidirectional"))
    )
    (net (code "43") (name "Net-(Q11-B)") (class "Default")
      (node (ref "D28") (pin "A") (pinfunction "A_A") (pintype "passive"))
      (node (ref "Q11") (pin "2") (pinfunction "B_2") (pintype "passive"))
      (node (ref "R22") (pin "1") (pinfunction "1_1") (pintype "passive"))
    )
    (net (code "44") (name "Net-(Q11-C)") (class "Default")
      (node (ref "C9") (pin "2") (pinfunction "2_2") (pintype "passive"))
      (node (ref "Q11") (pin "3") (pinfunction "C_3") (pintype "passive"))
      (node (ref "Q12") (pin "2") (pinfunction "B_2") (pintype "passive"))
      (node (ref "R24") (pin "2") (pinfunction "2_2") (pintype "passive"))
    )
    (net (code "45") (name "Net-(Q12-C)") (class "Default")
      (node (ref "D31") (pin "C") (pinfunction "C_C") (pintype "passive"))
      (node (ref "Q12") (pin "3") (pinfunction "C_3") (pintype "passive"))
      (node (ref "R25") (pin "2") (pinfunction "2_2") (pintype "passive"))
      (node (ref "U$2") (pin "K2") (pinfunction "1_K2") (pintype "bidirectional"))
    )
    (net (code "46") (name "Net-(Q13-B)") (class "Default")
      (node (ref "D34") (pin "A") (pinfunction "A_A") (pintype "passive"))
      (node (ref "Q13") (pin "2") (pinfunction "B_2") (pintype "passive"))
      (node (ref "R26") (pin "1") (pinfunction "1_1") (pintype "passive"))
    )
    (net (code "47") (name "Net-(Q13-C)") (class "Default")
      (node (ref "C10") (pin "2") (pinfunction "2_2") (pintype "passive"))
      (node (ref "Q13") (pin "3") (pinfunction "C_3") (pintype "passive"))
      (node (ref "Q14") (pin "2") (pinfunction "B_2") (pintype "passive"))
      (node (ref "R27") (pin "2") (pinfunction "2_2") (pintype "passive"))
    )
    (net (code "48") (name "Net-(Q14-C)") (class "Default")
      (node (ref "D35") (pin "C") (pinfunction "C_C") (pintype "passive"))
      (node (ref "Q14") (pin "3") (pinfunction "C_3") (pintype "passive"))
      (node (ref "R29") (pin "2") (pinfunction "2_2") (pintype "passive"))
      (node (ref "U$2") (pin "U2") (pinfunction "1_U2") (pintype "bidirectional"))
    )
    (net (code "49") (name "Net-(U$2D-1)") (class "Default")
      (node (ref "D5") (pin "A") (pinfunction "A_A") (pintype "passive"))
      (node (ref "U$2") (pin "D2") (pinfunction "1_D2") (pintype "bidirectional"))
    )
    (net (code "50") (name "Net-(U$2F-1)") (class "Default")
      (node (ref "D15") (pin "A") (pinfunction "A_A") (pintype "passive"))
      (node (ref "U$2") (pin "F2") (pinfunction "1_F2") (pintype "bidirectional"))
    )
    (net (code "51") (name "Net-(U$2H-1)") (class "Default")
      (node (ref "D25") (pin "A") (pinfunction "A_A") (pintype "passive"))
      (node (ref "U$2") (pin "J2") (pinfunction "1_J2") (pintype "bidirectional"))
    )
    (net (code "52") (name "Net-(U$2J-1)") (class "Default")
      (node (ref "D1") (pin "A") (pinfunction "A_A") (pintype "passive"))
      (node (ref "U$2") (pin "L2") (pinfunction "1_L2") (pintype "bidirectional"))
    )
    (net (code "53") (name "Net-(U$2L-1)") (class "Default")
      (node (ref "D10") (pin "A") (pinfunction "A_A") (pintype "passive"))
      (node (ref "U$2") (pin "N2") (pinfunction "1_N2") (pintype "bidirectional"))
    )
    (net (code "54") (name "Net-(U$2N-1)") (class "Default")
      (node (ref "D20") (pin "A") (pinfunction "A_A") (pintype "passive"))
      (node (ref "U$2") (pin "R2") (pinfunction "1_R2") (pintype "bidirectional"))
    )
    (net (code "55") (name "Net-(U$2P-1)") (class "Default")
      (node (ref "D30") (pin "A") (pinfunction "A_A") (pintype "passive"))
      (node (ref "U$2") (pin "T2") (pinfunction "1_T2") (pintype "bidirectional"))
    )
    (net (code "56") (name "VCC") (class "Default")
      (node (ref "C3") (pin "1") (pinfunction "1_1") (pintype "passive"))
      (node (ref "R10") (pin "2") (pinfunction "2_2") (pintype "passive"))
      (node (ref "R14") (pin "2") (pinfunction "2_2") (pintype "passive"))
      (node (ref "R18") (pin "2") (pinfunction "2_2") (pintype "passive"))
      (node (ref "R2") (pin "2") (pinfunction "2_2") (pintype "passive"))
      (node (ref "R22") (pin "2") (pinfunction "2_2") (pintype "passive"))
      (node (ref "R26") (pin "2") (pinfunction "2_2") (pintype "passive"))
      (node (ref "R6") (pin "2") (pinfunction "2_2") (pintype "passive"))
      (node (ref "U$2") (pin "A2") (pinfunction "1_A2") (pintype "bidirectional"))
    )
  )
)
